# PinWheelV2.net
KiCad netlist of a schematic drawn in Altium Designer
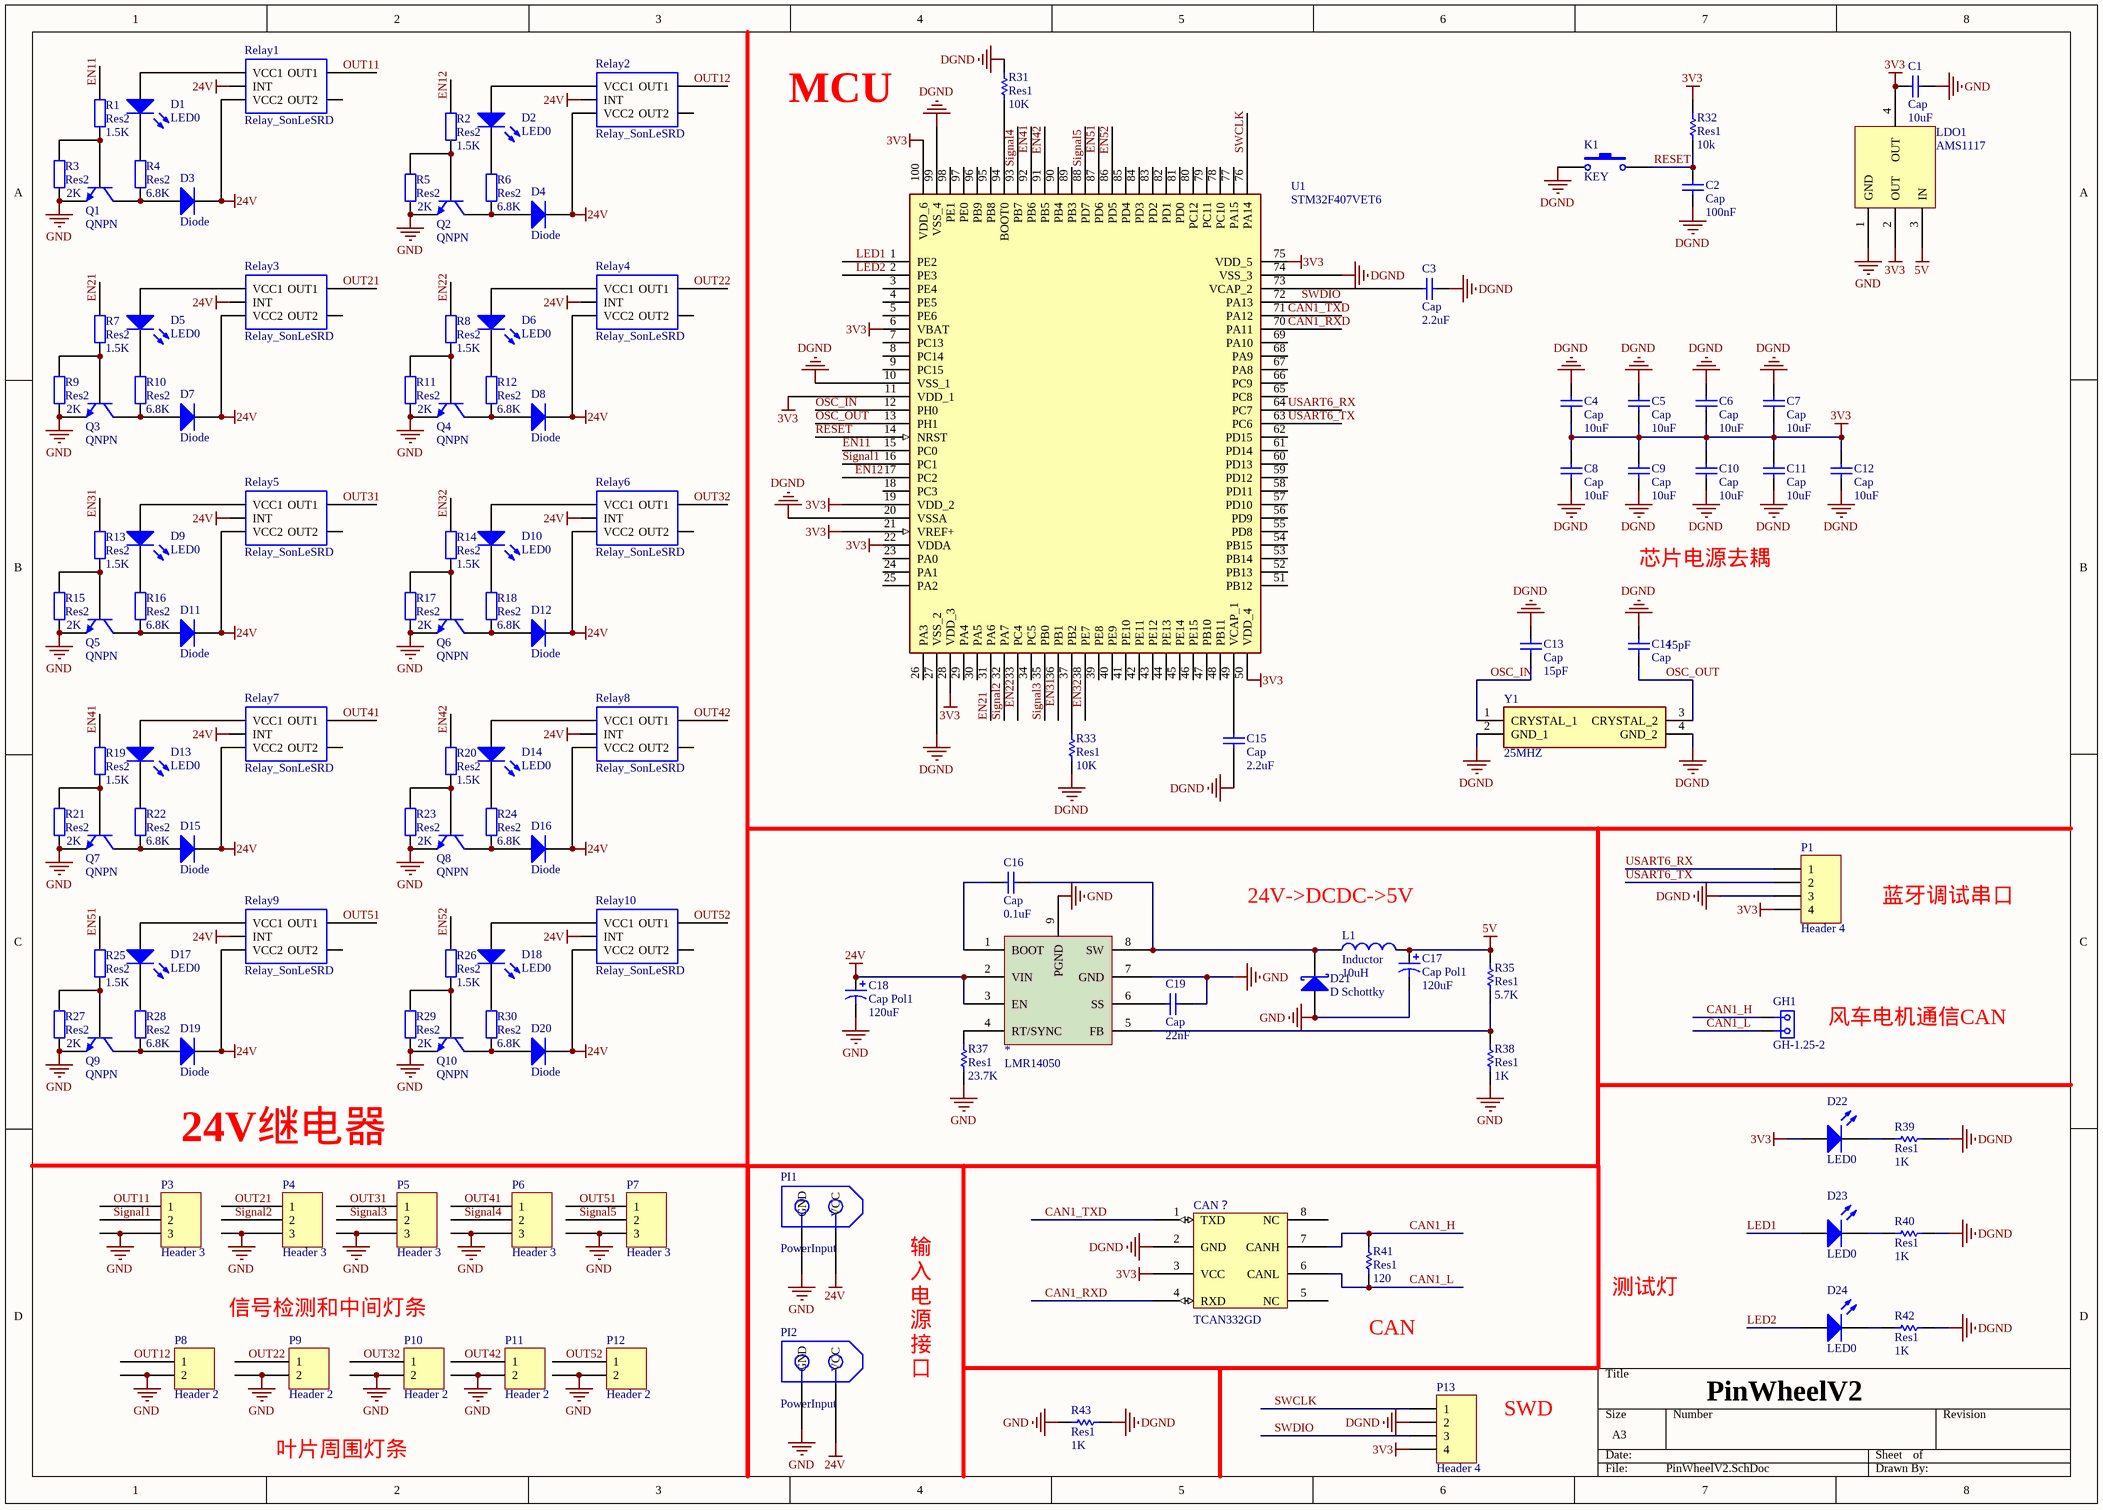
[diagram p0: PinWheelV2.SchDoc]

(export (version "E")
  (design (tool "Eeschema 10.0.6"))
  (components
    (comp (ref "*") (value "LMR14050") (footprint "LMR14050") (libsource (lib "PinWheel") (part "LMR14050")))
    (comp (ref "C1")
      (value "Cap")
      (footprint "R 0603")
      (description "Capacitor")
      (fields (field (name "ALTIUM_VALUE") "10uF") (field (name "PUBLISHER") "Altium Limited"))
      (libsource (lib "Miscellaneous Devices") (part "Cap"))
    )
    (comp (ref "C2")
      (value "Cap")
      (footprint "R 0603")
      (description "Capacitor")
      (fields (field (name "ALTIUM_VALUE") "100nF") (field (name "PUBLISHER") "Altium Limited"))
      (libsource (lib "Miscellaneous Devices") (part "Cap"))
    )
    (comp (ref "C3")
      (value "Cap")
      (footprint "R 0603")
      (description "Capacitor")
      (fields (field (name "ALTIUM_VALUE") "2.2uF") (field (name "PUBLISHER") "Altium Limited"))
      (libsource (lib "Miscellaneous Devices") (part "Cap"))
    )
    (comp (ref "C4")
      (value "Cap")
      (footprint "R 0603")
      (description "Capacitor")
      (fields (field (name "ALTIUM_VALUE") "10uF") (field (name "PUBLISHER") "Altium Limited"))
      (libsource (lib "Miscellaneous Devices") (part "Cap"))
    )
    (comp (ref "C5")
      (value "Cap")
      (footprint "R 0603")
      (description "Capacitor")
      (fields (field (name "ALTIUM_VALUE") "10uF") (field (name "PUBLISHER") "Altium Limited"))
      (libsource (lib "Miscellaneous Devices") (part "Cap"))
    )
    (comp (ref "C6")
      (value "Cap")
      (footprint "R 0603")
      (description "Capacitor")
      (fields (field (name "ALTIUM_VALUE") "10uF") (field (name "PUBLISHER") "Altium Limited"))
      (libsource (lib "Miscellaneous Devices") (part "Cap"))
    )
    (comp (ref "C7")
      (value "Cap")
      (footprint "R 0603")
      (description "Capacitor")
      (fields (field (name "ALTIUM_VALUE") "10uF") (field (name "PUBLISHER") "Altium Limited"))
      (libsource (lib "Miscellaneous Devices") (part "Cap"))
    )
    (comp (ref "C8")
      (value "Cap")
      (footprint "R 0603")
      (description "Capacitor")
      (fields (field (name "ALTIUM_VALUE") "10uF") (field (name "PUBLISHER") "Altium Limited"))
      (libsource (lib "Miscellaneous Devices") (part "Cap"))
    )
    (comp (ref "C9")
      (value "Cap")
      (footprint "R 0603")
      (description "Capacitor")
      (fields (field (name "ALTIUM_VALUE") "10uF") (field (name "PUBLISHER") "Altium Limited"))
      (libsource (lib "Miscellaneous Devices") (part "Cap"))
    )
    (comp (ref "C10")
      (value "Cap")
      (footprint "R 0603")
      (description "Capacitor")
      (fields (field (name "ALTIUM_VALUE") "10uF") (field (name "PUBLISHER") "Altium Limited"))
      (libsource (lib "Miscellaneous Devices") (part "Cap"))
    )
    (comp (ref "C11")
      (value "Cap")
      (footprint "R 0603")
      (description "Capacitor")
      (fields (field (name "ALTIUM_VALUE") "10uF") (field (name "PUBLISHER") "Altium Limited"))
      (libsource (lib "Miscellaneous Devices") (part "Cap"))
    )
    (comp (ref "C12")
      (value "Cap")
      (footprint "R 0603")
      (description "Capacitor")
      (fields (field (name "ALTIUM_VALUE") "10uF") (field (name "PUBLISHER") "Altium Limited"))
      (libsource (lib "Miscellaneous Devices") (part "Cap"))
    )
    (comp (ref "C13")
      (value "Cap")
      (footprint "R 0603")
      (description "Capacitor")
      (fields (field (name "ALTIUM_VALUE") "15pF") (field (name "PUBLISHER") "Altium Limited"))
      (libsource (lib "Miscellaneous Devices") (part "Cap"))
    )
    (comp (ref "C14")
      (value "Cap")
      (footprint "R 0603")
      (description "Capacitor")
      (fields (field (name "ALTIUM_VALUE") "15pF") (field (name "PUBLISHER") "Altium Limited"))
      (libsource (lib "Miscellaneous Devices") (part "Cap"))
    )
    (comp (ref "C15")
      (value "Cap")
      (footprint "R 0603")
      (description "Capacitor")
      (fields (field (name "ALTIUM_VALUE") "2.2uF") (field (name "PUBLISHER") "Altium Limited"))
      (libsource (lib "Miscellaneous Devices") (part "Cap"))
    )
    (comp (ref "C16")
      (value "Cap")
      (footprint "R 0603")
      (description "Capacitor")
      (fields (field (name "ALTIUM_VALUE") "0.1uF") (field (name "PUBLISHER") "Altium Limited"))
      (libsource (lib "Miscellaneous Devices") (part "Cap"))
    )
    (comp (ref "C17")
      (value "Cap Pol1")
      (footprint "Cap+8*11")
      (description "Polarized Capacitor (Radial)")
      (fields (field (name "ALTIUM_VALUE") "120uF") (field (name "PUBLISHER") "Altium Limited"))
      (libsource (lib "Miscellaneous Devices") (part "Cap Pol1"))
    )
    (comp (ref "C18")
      (value "Cap Pol1")
      (footprint "Cap+8*11")
      (description "Polarized Capacitor (Radial)")
      (fields (field (name "ALTIUM_VALUE") "120uF") (field (name "PUBLISHER") "Altium Limited"))
      (libsource (lib "Miscellaneous Devices") (part "Cap Pol1"))
    )
    (comp (ref "C19")
      (value "Cap")
      (footprint "R 0603")
      (description "Capacitor")
      (fields (field (name "ALTIUM_VALUE") "22nF") (field (name "PUBLISHER") "Altium Limited"))
      (libsource (lib "Miscellaneous Devices") (part "Cap"))
    )
    (comp (ref "CAN？")
      (value "TCAN332GD")
      (footprint "LMR14050")
      (libsource (lib "PinWheel") (part "TCAN332GD"))
    )
    (comp (ref "D1")
      (value "LED0")
      (footprint "LED 0603")
      (description "Typical INFRARED GaAs LED")
      (fields (field (name "PUBLISHER") "Altium Limited"))
      (libsource (lib "Miscellaneous Devices") (part "LED0"))
    )
    (comp (ref "D2")
      (value "LED0")
      (footprint "LED 0603")
      (description "Typical INFRARED GaAs LED")
      (fields (field (name "PUBLISHER") "Altium Limited"))
      (libsource (lib "Miscellaneous Devices") (part "LED0"))
    )
    (comp (ref "D3")
      (value "Diode")
      (footprint "1N4007 D")
      (description "Default Diode")
      (fields (field (name "PUBLISHER") "Altium Limited"))
      (libsource (lib "Miscellaneous Devices") (part "Diode"))
    )
    (comp (ref "D4")
      (value "Diode")
      (footprint "1N4007 D")
      (description "Default Diode")
      (fields (field (name "PUBLISHER") "Altium Limited"))
      (libsource (lib "Miscellaneous Devices") (part "Diode"))
    )
    (comp (ref "D5")
      (value "LED0")
      (footprint "LED 0603")
      (description "Typical INFRARED GaAs LED")
      (fields (field (name "PUBLISHER") "Altium Limited"))
      (libsource (lib "Miscellaneous Devices") (part "LED0"))
    )
    (comp (ref "D6")
      (value "LED0")
      (footprint "LED 0603")
      (description "Typical INFRARED GaAs LED")
      (fields (field (name "PUBLISHER") "Altium Limited"))
      (libsource (lib "Miscellaneous Devices") (part "LED0"))
    )
    (comp (ref "D7")
      (value "Diode")
      (footprint "1N4007 D")
      (description "Default Diode")
      (fields (field (name "PUBLISHER") "Altium Limited"))
      (libsource (lib "Miscellaneous Devices") (part "Diode"))
    )
    (comp (ref "D8")
      (value "Diode")
      (footprint "1N4007 D")
      (description "Default Diode")
      (fields (field (name "PUBLISHER") "Altium Limited"))
      (libsource (lib "Miscellaneous Devices") (part "Diode"))
    )
    (comp (ref "D9")
      (value "LED0")
      (footprint "LED 0603")
      (description "Typical INFRARED GaAs LED")
      (fields (field (name "PUBLISHER") "Altium Limited"))
      (libsource (lib "Miscellaneous Devices") (part "LED0"))
    )
    (comp (ref "D10")
      (value "LED0")
      (footprint "LED 0603")
      (description "Typical INFRARED GaAs LED")
      (fields (field (name "PUBLISHER") "Altium Limited"))
      (libsource (lib "Miscellaneous Devices") (part "LED0"))
    )
    (comp (ref "D11")
      (value "Diode")
      (footprint "1N4007 D")
      (description "Default Diode")
      (fields (field (name "PUBLISHER") "Altium Limited"))
      (libsource (lib "Miscellaneous Devices") (part "Diode"))
    )
    (comp (ref "D12")
      (value "Diode")
      (footprint "1N4007 D")
      (description "Default Diode")
      (fields (field (name "PUBLISHER") "Altium Limited"))
      (libsource (lib "Miscellaneous Devices") (part "Diode"))
    )
    (comp (ref "D13")
      (value "LED0")
      (footprint "LED 0603")
      (description "Typical INFRARED GaAs LED")
      (fields (field (name "PUBLISHER") "Altium Limited"))
      (libsource (lib "Miscellaneous Devices") (part "LED0"))
    )
    (comp (ref "D14")
      (value "LED0")
      (footprint "LED 0603")
      (description "Typical INFRARED GaAs LED")
      (fields (field (name "PUBLISHER") "Altium Limited"))
      (libsource (lib "Miscellaneous Devices") (part "LED0"))
    )
    (comp (ref "D15")
      (value "Diode")
      (footprint "1N4007 D")
      (description "Default Diode")
      (fields (field (name "PUBLISHER") "Altium Limited"))
      (libsource (lib "Miscellaneous Devices") (part "Diode"))
    )
    (comp (ref "D16")
      (value "Diode")
      (footprint "1N4007 D")
      (description "Default Diode")
      (fields (field (name "PUBLISHER") "Altium Limited"))
      (libsource (lib "Miscellaneous Devices") (part "Diode"))
    )
    (comp (ref "D17")
      (value "LED0")
      (footprint "LED 0603")
      (description "Typical INFRARED GaAs LED")
      (fields (field (name "PUBLISHER") "Altium Limited"))
      (libsource (lib "Miscellaneous Devices") (part "LED0"))
    )
    (comp (ref "D18")
      (value "LED0")
      (footprint "LED 0603")
      (description "Typical INFRARED GaAs LED")
      (fields (field (name "PUBLISHER") "Altium Limited"))
      (libsource (lib "Miscellaneous Devices") (part "LED0"))
    )
    (comp (ref "D19")
      (value "Diode")
      (footprint "1N4007 D")
      (description "Default Diode")
      (fields (field (name "PUBLISHER") "Altium Limited"))
      (libsource (lib "Miscellaneous Devices") (part "Diode"))
    )
    (comp (ref "D20")
      (value "Diode")
      (footprint "1N4007 D")
      (description "Default Diode")
      (fields (field (name "PUBLISHER") "Altium Limited"))
      (libsource (lib "Miscellaneous Devices") (part "Diode"))
    )
    (comp (ref "D21")
      (value "D Schottky")
      (footprint "SMB")
      (description "Schottky Diode")
      (fields (field (name "PUBLISHER") "Altium Limited"))
      (libsource (lib "Miscellaneous Devices") (part "D Schottky"))
    )
    (comp (ref "D22")
      (value "LED0")
      (footprint "LED 0603")
      (description "Typical INFRARED GaAs LED")
      (fields (field (name "PUBLISHER") "Altium Limited"))
      (libsource (lib "Miscellaneous Devices") (part "LED0"))
    )
    (comp (ref "D23")
      (value "LED0")
      (footprint "LED 0603")
      (description "Typical INFRARED GaAs LED")
      (fields (field (name "PUBLISHER") "Altium Limited"))
      (libsource (lib "Miscellaneous Devices") (part "LED0"))
    )
    (comp (ref "D24")
      (value "LED0")
      (footprint "LED 0603")
      (description "Typical INFRARED GaAs LED")
      (fields (field (name "PUBLISHER") "Altium Limited"))
      (libsource (lib "Miscellaneous Devices") (part "LED0"))
    )
    (comp (ref "GH1")
      (value "GH-1.25-2")
      (footprint "GH1.25_2P")
      (libsource (lib "Personal_Integrated_Library") (part "GH-1.25-2"))
    )
    (comp (ref "K1") (value "KEY") (footprint "keySMD3.5*6") (libsource (lib "PinWheel") (part "KEY")))
    (comp (ref "L1")
      (value "Inductor")
      (footprint "L 3.5*3*2.1")
      (fields (field (name "ALTIUM_VALUE") "10uH") (field (name "PUBLISHER") "Altium Limited"))
      (libsource (lib "Miscellaneous Devices") (part "Inductor"))
    )
    (comp (ref "LDO1")
      (value "AMS1117")
      (footprint "AMS1117 3V3")
      (libsource (lib "Personal_Integrated_Library") (part "AMS1117"))
    )
    (comp (ref "P1")
      (value "Header 4")
      (footprint "HDR1X4")
      (description "Header, 4-Pin")
      (fields (field (name "PUBLISHER") "Altium Limited"))
      (libsource (lib "Miscellaneous Connectors") (part "Header 4"))
    )
    (comp (ref "P3")
      (value "Header 3")
      (footprint "螺旋端子 3P3.81")
      (description "Header, 3-Pin")
      (fields (field (name "PUBLISHER") "Altium Limited"))
      (libsource (lib "Miscellaneous Connectors") (part "Header 3"))
    )
    (comp (ref "P4")
      (value "Header 3")
      (footprint "螺旋端子 3P3.81")
      (description "Header, 3-Pin")
      (fields (field (name "PUBLISHER") "Altium Limited"))
      (libsource (lib "Miscellaneous Connectors") (part "Header 3"))
    )
    (comp (ref "P5")
      (value "Header 3")
      (footprint "螺旋端子 3P3.81")
      (description "Header, 3-Pin")
      (fields (field (name "PUBLISHER") "Altium Limited"))
      (libsource (lib "Miscellaneous Connectors") (part "Header 3"))
    )
    (comp (ref "P6")
      (value "Header 3")
      (footprint "螺旋端子 3P3.81")
      (description "Header, 3-Pin")
      (fields (field (name "PUBLISHER") "Altium Limited"))
      (libsource (lib "Miscellaneous Connectors") (part "Header 3"))
    )
    (comp (ref "P7")
      (value "Header 3")
      (footprint "螺旋端子 3P3.81")
      (description "Header, 3-Pin")
      (fields (field (name "PUBLISHER") "Altium Limited"))
      (libsource (lib "Miscellaneous Connectors") (part "Header 3"))
    )
    (comp (ref "P8")
      (value "Header 2")
      (footprint "螺旋端子 2P3.81")
      (description "Header, 2-Pin")
      (fields (field (name "PUBLISHER") "Altium Limited"))
      (libsource (lib "Miscellaneous Connectors") (part "Header 2"))
    )
    (comp (ref "P9")
      (value "Header 2")
      (footprint "螺旋端子 2P3.81")
      (description "Header, 2-Pin")
      (fields (field (name "PUBLISHER") "Altium Limited"))
      (libsource (lib "Miscellaneous Connectors") (part "Header 2"))
    )
    (comp (ref "P10")
      (value "Header 2")
      (footprint "螺旋端子 2P3.81")
      (description "Header, 2-Pin")
      (fields (field (name "PUBLISHER") "Altium Limited"))
      (libsource (lib "Miscellaneous Connectors") (part "Header 2"))
    )
    (comp (ref "P11")
      (value "Header 2")
      (footprint "螺旋端子 2P3.81")
      (description "Header, 2-Pin")
      (fields (field (name "PUBLISHER") "Altium Limited"))
      (libsource (lib "Miscellaneous Connectors") (part "Header 2"))
    )
    (comp (ref "P12")
      (value "Header 2")
      (footprint "螺旋端子 2P3.81")
      (description "Header, 2-Pin")
      (fields (field (name "PUBLISHER") "Altium Limited"))
      (libsource (lib "Miscellaneous Connectors") (part "Header 2"))
    )
    (comp (ref "P13")
      (value "Header 4")
      (footprint "HDR1X4")
      (description "Header, 4-Pin")
      (fields (field (name "PUBLISHER") "Altium Limited"))
      (libsource (lib "Miscellaneous Connectors") (part "Header 4"))
    )
    (comp (ref "PI1") (value "PowerInput") (footprint "XT30") (libsource (lib "Schlib1") (part "PowerInput")))
    (comp (ref "PI2") (value "PowerInput") (footprint "XT30") (libsource (lib "Schlib1") (part "PowerInput")))
    (comp (ref "Q1")
      (value "QNPN")
      (footprint "MMBT2222A")
      (description "NPN Bipolar Transistor")
      (fields (field (name "PUBLISHER") "Altium Limited"))
      (libsource (lib "Miscellaneous Devices") (part "QNPN"))
    )
    (comp (ref "Q2")
      (value "QNPN")
      (footprint "MMBT2222A")
      (description "NPN Bipolar Transistor")
      (fields (field (name "PUBLISHER") "Altium Limited"))
      (libsource (lib "Miscellaneous Devices") (part "QNPN"))
    )
    (comp (ref "Q3")
      (value "QNPN")
      (footprint "MMBT2222A")
      (description "NPN Bipolar Transistor")
      (fields (field (name "PUBLISHER") "Altium Limited"))
      (libsource (lib "Miscellaneous Devices") (part "QNPN"))
    )
    (comp (ref "Q4")
      (value "QNPN")
      (footprint "MMBT2222A")
      (description "NPN Bipolar Transistor")
      (fields (field (name "PUBLISHER") "Altium Limited"))
      (libsource (lib "Miscellaneous Devices") (part "QNPN"))
    )
    (comp (ref "Q5")
      (value "QNPN")
      (footprint "MMBT2222A")
      (description "NPN Bipolar Transistor")
      (fields (field (name "PUBLISHER") "Altium Limited"))
      (libsource (lib "Miscellaneous Devices") (part "QNPN"))
    )
    (comp (ref "Q6")
      (value "QNPN")
      (footprint "MMBT2222A")
      (description "NPN Bipolar Transistor")
      (fields (field (name "PUBLISHER") "Altium Limited"))
      (libsource (lib "Miscellaneous Devices") (part "QNPN"))
    )
    (comp (ref "Q7")
      (value "QNPN")
      (footprint "MMBT2222A")
      (description "NPN Bipolar Transistor")
      (fields (field (name "PUBLISHER") "Altium Limited"))
      (libsource (lib "Miscellaneous Devices") (part "QNPN"))
    )
    (comp (ref "Q8")
      (value "QNPN")
      (footprint "MMBT2222A")
      (description "NPN Bipolar Transistor")
      (fields (field (name "PUBLISHER") "Altium Limited"))
      (libsource (lib "Miscellaneous Devices") (part "QNPN"))
    )
    (comp (ref "Q9")
      (value "QNPN")
      (footprint "MMBT2222A")
      (description "NPN Bipolar Transistor")
      (fields (field (name "PUBLISHER") "Altium Limited"))
      (libsource (lib "Miscellaneous Devices") (part "QNPN"))
    )
    (comp (ref "Q10")
      (value "QNPN")
      (footprint "MMBT2222A")
      (description "NPN Bipolar Transistor")
      (fields (field (name "PUBLISHER") "Altium Limited"))
      (libsource (lib "Miscellaneous Devices") (part "QNPN"))
    )
    (comp (ref "R1")
      (value "Res2")
      (footprint "R 0603")
      (description "Resistor")
      (fields (field (name "ALTIUM_VALUE") "1.5K") (field (name "PUBLISHER") "Altium Limited"))
      (libsource (lib "Miscellaneous Devices") (part "Res2"))
    )
    (comp (ref "R2")
      (value "Res2")
      (footprint "R 0603")
      (description "Resistor")
      (fields (field (name "ALTIUM_VALUE") "1.5K") (field (name "PUBLISHER") "Altium Limited"))
      (libsource (lib "Miscellaneous Devices") (part "Res2"))
    )
    (comp (ref "R3")
      (value "Res2")
      (footprint "R 0603")
      (description "Resistor")
      (fields (field (name "ALTIUM_VALUE") "2K") (field (name "PUBLISHER") "Altium Limited"))
      (libsource (lib "Miscellaneous Devices") (part "Res2"))
    )
    (comp (ref "R4")
      (value "Res2")
      (footprint "R 0603")
      (description "Resistor")
      (fields (field (name "ALTIUM_VALUE") "6.8K") (field (name "PUBLISHER") "Altium Limited"))
      (libsource (lib "Miscellaneous Devices") (part "Res2"))
    )
    (comp (ref "R5")
      (value "Res2")
      (footprint "R 0603")
      (description "Resistor")
      (fields (field (name "ALTIUM_VALUE") "2K") (field (name "PUBLISHER") "Altium Limited"))
      (libsource (lib "Miscellaneous Devices") (part "Res2"))
    )
    (comp (ref "R6")
      (value "Res2")
      (footprint "R 0603")
      (description "Resistor")
      (fields (field (name "ALTIUM_VALUE") "6.8K") (field (name "PUBLISHER") "Altium Limited"))
      (libsource (lib "Miscellaneous Devices") (part "Res2"))
    )
    (comp (ref "R7")
      (value "Res2")
      (footprint "R 0603")
      (description "Resistor")
      (fields (field (name "ALTIUM_VALUE") "1.5K") (field (name "PUBLISHER") "Altium Limited"))
      (libsource (lib "Miscellaneous Devices") (part "Res2"))
    )
    (comp (ref "R8")
      (value "Res2")
      (footprint "R 0603")
      (description "Resistor")
      (fields (field (name "ALTIUM_VALUE") "1.5K") (field (name "PUBLISHER") "Altium Limited"))
      (libsource (lib "Miscellaneous Devices") (part "Res2"))
    )
    (comp (ref "R9")
      (value "Res2")
      (footprint "R 0603")
      (description "Resistor")
      (fields (field (name "ALTIUM_VALUE") "2K") (field (name "PUBLISHER") "Altium Limited"))
      (libsource (lib "Miscellaneous Devices") (part "Res2"))
    )
    (comp (ref "R10")
      (value "Res2")
      (footprint "R 0603")
      (description "Resistor")
      (fields (field (name "ALTIUM_VALUE") "6.8K") (field (name "PUBLISHER") "Altium Limited"))
      (libsource (lib "Miscellaneous Devices") (part "Res2"))
    )
    (comp (ref "R11")
      (value "Res2")
      (footprint "R 0603")
      (description "Resistor")
      (fields (field (name "ALTIUM_VALUE") "2K") (field (name "PUBLISHER") "Altium Limited"))
      (libsource (lib "Miscellaneous Devices") (part "Res2"))
    )
    (comp (ref "R12")
      (value "Res2")
      (footprint "R 0603")
      (description "Resistor")
      (fields (field (name "ALTIUM_VALUE") "6.8K") (field (name "PUBLISHER") "Altium Limited"))
      (libsource (lib "Miscellaneous Devices") (part "Res2"))
    )
    (comp (ref "R13")
      (value "Res2")
      (footprint "R 0603")
      (description "Resistor")
      (fields (field (name "ALTIUM_VALUE") "1.5K") (field (name "PUBLISHER") "Altium Limited"))
      (libsource (lib "Miscellaneous Devices") (part "Res2"))
    )
    (comp (ref "R14")
      (value "Res2")
      (footprint "R 0603")
      (description "Resistor")
      (fields (field (name "ALTIUM_VALUE") "1.5K") (field (name "PUBLISHER") "Altium Limited"))
      (libsource (lib "Miscellaneous Devices") (part "Res2"))
    )
    (comp (ref "R15")
      (value "Res2")
      (footprint "R 0603")
      (description "Resistor")
      (fields (field (name "ALTIUM_VALUE") "2K") (field (name "PUBLISHER") "Altium Limited"))
      (libsource (lib "Miscellaneous Devices") (part "Res2"))
    )
    (comp (ref "R16")
      (value "Res2")
      (footprint "R 0603")
      (description "Resistor")
      (fields (field (name "ALTIUM_VALUE") "6.8K") (field (name "PUBLISHER") "Altium Limited"))
      (libsource (lib "Miscellaneous Devices") (part "Res2"))
    )
    (comp (ref "R17")
      (value "Res2")
      (footprint "R 0603")
      (description "Resistor")
      (fields (field (name "ALTIUM_VALUE") "2K") (field (name "PUBLISHER") "Altium Limited"))
      (libsource (lib "Miscellaneous Devices") (part "Res2"))
    )
    (comp (ref "R18")
      (value "Res2")
      (footprint "R 0603")
      (description "Resistor")
      (fields (field (name "ALTIUM_VALUE") "6.8K") (field (name "PUBLISHER") "Altium Limited"))
      (libsource (lib "Miscellaneous Devices") (part "Res2"))
    )
    (comp (ref "R19")
      (value "Res2")
      (footprint "R 0603")
      (description "Resistor")
      (fields (field (name "ALTIUM_VALUE") "1.5K") (field (name "PUBLISHER") "Altium Limited"))
      (libsource (lib "Miscellaneous Devices") (part "Res2"))
    )
    (comp (ref "R20")
      (value "Res2")
      (footprint "R 0603")
      (description "Resistor")
      (fields (field (name "ALTIUM_VALUE") "1.5K") (field (name "PUBLISHER") "Altium Limited"))
      (libsource (lib "Miscellaneous Devices") (part "Res2"))
    )
    (comp (ref "R21")
      (value "Res2")
      (footprint "R 0603")
      (description "Resistor")
      (fields (field (name "ALTIUM_VALUE") "2K") (field (name "PUBLISHER") "Altium Limited"))
      (libsource (lib "Miscellaneous Devices") (part "Res2"))
    )
    (comp (ref "R22")
      (value "Res2")
      (footprint "R 0603")
      (description "Resistor")
      (fields (field (name "ALTIUM_VALUE") "6.8K") (field (name "PUBLISHER") "Altium Limited"))
      (libsource (lib "Miscellaneous Devices") (part "Res2"))
    )
    (comp (ref "R23")
      (value "Res2")
      (footprint "R 0603")
      (description "Resistor")
      (fields (field (name "ALTIUM_VALUE") "2K") (field (name "PUBLISHER") "Altium Limited"))
      (libsource (lib "Miscellaneous Devices") (part "Res2"))
    )
    (comp (ref "R24")
      (value "Res2")
      (footprint "R 0603")
      (description "Resistor")
      (fields (field (name "ALTIUM_VALUE") "6.8K") (field (name "PUBLISHER") "Altium Limited"))
      (libsource (lib "Miscellaneous Devices") (part "Res2"))
    )
    (comp (ref "R25")
      (value "Res2")
      (footprint "R 0603")
      (description "Resistor")
      (fields (field (name "ALTIUM_VALUE") "1.5K") (field (name "PUBLISHER") "Altium Limited"))
      (libsource (lib "Miscellaneous Devices") (part "Res2"))
    )
    (comp (ref "R26")
      (value "Res2")
      (footprint "R 0603")
      (description "Resistor")
      (fields (field (name "ALTIUM_VALUE") "1.5K") (field (name "PUBLISHER") "Altium Limited"))
      (libsource (lib "Miscellaneous Devices") (part "Res2"))
    )
    (comp (ref "R27")
      (value "Res2")
      (footprint "R 0603")
      (description "Resistor")
      (fields (field (name "ALTIUM_VALUE") "2K") (field (name "PUBLISHER") "Altium Limited"))
      (libsource (lib "Miscellaneous Devices") (part "Res2"))
    )
    (comp (ref "R28")
      (value "Res2")
      (footprint "R 0603")
      (description "Resistor")
      (fields (field (name "ALTIUM_VALUE") "6.8K") (field (name "PUBLISHER") "Altium Limited"))
      (libsource (lib "Miscellaneous Devices") (part "Res2"))
    )
    (comp (ref "R29")
      (value "Res2")
      (footprint "R 0603")
      (description "Resistor")
      (fields (field (name "ALTIUM_VALUE") "2K") (field (name "PUBLISHER") "Altium Limited"))
      (libsource (lib "Miscellaneous Devices") (part "Res2"))
    )
    (comp (ref "R30")
      (value "Res2")
      (footprint "R 0603")
      (description "Resistor")
      (fields (field (name "ALTIUM_VALUE") "6.8K") (field (name "PUBLISHER") "Altium Limited"))
      (libsource (lib "Miscellaneous Devices") (part "Res2"))
    )
    (comp (ref "R31")
      (value "Res1")
      (footprint "R 0603")
      (description "Resistor")
      (fields (field (name "ALTIUM_VALUE") "10K") (field (name "PUBLISHER") "Altium Limited"))
      (libsource (lib "Miscellaneous Devices") (part "Res1"))
    )
    (comp (ref "R32")
      (value "Res1")
      (footprint "R 0603")
      (description "Resistor")
      (fields (field (name "ALTIUM_VALUE") "10k") (field (name "PUBLISHER") "Altium Limited"))
      (libsource (lib "Miscellaneous Devices") (part "Res1"))
    )
    (comp (ref "R33")
      (value "Res1")
      (footprint "R 0603")
      (description "Resistor")
      (fields (field (name "ALTIUM_VALUE") "10K") (field (name "PUBLISHER") "Altium Limited"))
      (libsource (lib "Miscellaneous Devices") (part "Res1"))
    )
    (comp (ref "R35")
      (value "Res1")
      (footprint "R 0603")
      (description "Resistor")
      (fields (field (name "ALTIUM_VALUE") "5.7K") (field (name "PUBLISHER") "Altium Limited"))
      (libsource (lib "Miscellaneous Devices") (part "Res1"))
    )
    (comp (ref "R37")
      (value "Res1")
      (footprint "R 0603")
      (description "Resistor")
      (fields (field (name "ALTIUM_VALUE") "23.7K") (field (name "PUBLISHER") "Altium Limited"))
      (libsource (lib "Miscellaneous Devices") (part "Res1"))
    )
    (comp (ref "R38")
      (value "Res1")
      (footprint "R 0603")
      (description "Resistor")
      (fields (field (name "ALTIUM_VALUE") "1K") (field (name "PUBLISHER") "Altium Limited"))
      (libsource (lib "Miscellaneous Devices") (part "Res1"))
    )
    (comp (ref "R39")
      (value "Res1")
      (footprint "R 0603")
      (description "Resistor")
      (fields (field (name "ALTIUM_VALUE") "1K") (field (name "PUBLISHER") "Altium Limited"))
      (libsource (lib "Miscellaneous Devices") (part "Res1"))
    )
    (comp (ref "R40")
      (value "Res1")
      (footprint "R 0603")
      (description "Resistor")
      (fields (field (name "ALTIUM_VALUE") "1K") (field (name "PUBLISHER") "Altium Limited"))
      (libsource (lib "Miscellaneous Devices") (part "Res1"))
    )
    (comp (ref "R41")
      (value "Res1")
      (footprint "R 0603")
      (description "Resistor")
      (fields (field (name "ALTIUM_VALUE") "120") (field (name "PUBLISHER") "Altium Limited"))
      (libsource (lib "Miscellaneous Devices") (part "Res1"))
    )
    (comp (ref "R42")
      (value "Res1")
      (footprint "R 0603")
      (description "Resistor")
      (fields (field (name "ALTIUM_VALUE") "1K") (field (name "PUBLISHER") "Altium Limited"))
      (libsource (lib "Miscellaneous Devices") (part "Res1"))
    )
    (comp (ref "R43")
      (value "Res1")
      (footprint "R 0603")
      (description "Resistor")
      (fields (field (name "ALTIUM_VALUE") "1K") (field (name "PUBLISHER") "Altium Limited"))
      (libsource (lib "Miscellaneous Devices") (part "Res1"))
    )
    (comp (ref "Relay1")
      (value "Relay_SonLeSRD")
      (footprint "RePlay_SonLe")
      (libsource (lib "Schlib1") (part "Relay_SonLeSRD"))
    )
    (comp (ref "Relay2")
      (value "Relay_SonLeSRD")
      (footprint "RePlay_SonLe")
      (libsource (lib "Schlib1") (part "Relay_SonLeSRD"))
    )
    (comp (ref "Relay3")
      (value "Relay_SonLeSRD")
      (footprint "RePlay_SonLe")
      (libsource (lib "Schlib1") (part "Relay_SonLeSRD"))
    )
    (comp (ref "Relay4")
      (value "Relay_SonLeSRD")
      (footprint "RePlay_SonLe")
      (libsource (lib "Schlib1") (part "Relay_SonLeSRD"))
    )
    (comp (ref "Relay5")
      (value "Relay_SonLeSRD")
      (footprint "RePlay_SonLe")
      (libsource (lib "Schlib1") (part "Relay_SonLeSRD"))
    )
    (comp (ref "Relay6")
      (value "Relay_SonLeSRD")
      (footprint "RePlay_SonLe")
      (libsource (lib "Schlib1") (part "Relay_SonLeSRD"))
    )
    (comp (ref "Relay7")
      (value "Relay_SonLeSRD")
      (footprint "RePlay_SonLe")
      (libsource (lib "Schlib1") (part "Relay_SonLeSRD"))
    )
    (comp (ref "Relay8")
      (value "Relay_SonLeSRD")
      (footprint "RePlay_SonLe")
      (libsource (lib "Schlib1") (part "Relay_SonLeSRD"))
    )
    (comp (ref "Relay9")
      (value "Relay_SonLeSRD")
      (footprint "RePlay_SonLe")
      (libsource (lib "Schlib1") (part "Relay_SonLeSRD"))
    )
    (comp (ref "Relay10")
      (value "Relay_SonLeSRD")
      (footprint "RePlay_SonLe")
      (libsource (lib "Schlib1") (part "Relay_SonLeSRD"))
    )
    (comp (ref "U1")
      (value "STM32F407VET6")
      (footprint "STM32F407VET6")
      (libsource (lib "PinWheel") (part "STM32F407VET6"))
    )
    (comp (ref "Y1")
      (value "25MHZ")
      (footprint "晶振 3.2*2.5")
      (description "Crystal or Oscillator")
      (fields
        (field (name "MOUSER PART NUMBER") "815-M11AIG-25-4ZT3")
        (field (name "MANUFACTURER_PART_NUMBER") "ABM11AIG-25.000MHZ-4Z-T3")
      )
      (libsource (lib "SamacSys") (part "ABM11AIG-25.000MHZ-4Z-T3"))
    )
  )
  (nets
    (net (code "1") (name "/CAN1_H") (class "Default")
      (node (ref "CAN？") (pin "7") (pinfunction "CANH_7") (pintype "power_in"))
      (node (ref "GH1") (pin "1") (pinfunction "1_1") (pintype "power_in"))
      (node (ref "R41") (pin "2") (pinfunction "2_2") (pintype "passive"))
    )
    (net (code "2") (name "/CAN1_L") (class "Default")
      (node (ref "CAN？") (pin "6") (pinfunction "CANL_6") (pintype "power_in"))
      (node (ref "GH1") (pin "2") (pinfunction "2_2") (pintype "power_in"))
      (node (ref "R41") (pin "1") (pinfunction "1_1") (pintype "passive"))
    )
    (net (code "3") (name "/CAN1_RXD") (class "Default")
      (node (ref "CAN？") (pin "4") (pinfunction "RXD_4") (pintype "bidirectional"))
      (node (ref "U1") (pin "70") (pinfunction "PA11_70") (pintype "passive"))
    )
    (net (code "4") (name "/CAN1_TXD") (class "Default")
      (node (ref "CAN？") (pin "1") (pinfunction "TXD_1") (pintype "bidirectional"))
      (node (ref "U1") (pin "71") (pinfunction "PA12_71") (pintype "passive"))
    )
    (net (code "5") (name "/EN11") (class "Default")
      (node (ref "R1") (pin "2") (pinfunction "2_2") (pintype "passive"))
      (node (ref "U1") (pin "15") (pinfunction "PC0_15") (pintype "passive"))
    )
    (net (code "6") (name "/EN12") (class "Default")
      (node (ref "R2") (pin "2") (pinfunction "2_2") (pintype "passive"))
      (node (ref "U1") (pin "17") (pinfunction "PC2_17") (pintype "passive"))
    )
    (net (code "7") (name "/EN21") (class "Default")
      (node (ref "R7") (pin "2") (pinfunction "2_2") (pintype "passive"))
      (node (ref "U1") (pin "31") (pinfunction "PA6_31") (pintype "passive"))
    )
    (net (code "8") (name "/EN22") (class "Default")
      (node (ref "R8") (pin "2") (pinfunction "2_2") (pintype "passive"))
      (node (ref "U1") (pin "33") (pinfunction "PC4_33") (pintype "passive"))
    )
    (net (code "9") (name "/EN31") (class "Default")
      (node (ref "R13") (pin "2") (pinfunction "2_2") (pintype "passive"))
      (node (ref "U1") (pin "36") (pinfunction "PB1_36") (pintype "passive"))
    )
    (net (code "10") (name "/EN32") (class "Default")
      (node (ref "R14") (pin "2") (pinfunction "2_2") (pintype "passive"))
      (node (ref "U1") (pin "38") (pinfunction "PE7_38") (pintype "passive"))
    )
    (net (code "11") (name "/EN41") (class "Default")
      (node (ref "R19") (pin "2") (pinfunction "2_2") (pintype "passive"))
      (node (ref "U1") (pin "92") (pinfunction "PB6_92") (pintype "passive"))
    )
    (net (code "12") (name "/EN42") (class "Default")
      (node (ref "R20") (pin "2") (pinfunction "2_2") (pintype "passive"))
      (node (ref "U1") (pin "91") (pinfunction "PB5_91") (pintype "passive"))
    )
    (net (code "13") (name "/EN51") (class "Default")
      (node (ref "R25") (pin "2") (pinfunction "2_2") (pintype "passive"))
      (node (ref "U1") (pin "87") (pinfunction "PD6_87") (pintype "passive"))
    )
    (net (code "14") (name "/EN52") (class "Default")
      (node (ref "R26") (pin "2") (pinfunction "2_2") (pintype "passive"))
      (node (ref "U1") (pin "86") (pinfunction "PD5_86") (pintype "passive"))
    )
    (net (code "15") (name "/LED1") (class "Default")
      (node (ref "D23") (pin "1") (pinfunction "A_1") (pintype "passive"))
      (node (ref "U1") (pin "1") (pinfunction "PE2_1") (pintype "passive"))
    )
    (net (code "16") (name "/LED2") (class "Default")
      (node (ref "D24") (pin "1") (pinfunction "A_1") (pintype "passive"))
      (node (ref "U1") (pin "2") (pinfunction "PE3_2") (pintype "passive"))
    )
    (net (code "17") (name "/OSC_IN") (class "Default")
      (node (ref "C13") (pin "1") (pinfunction "1_1") (pintype "passive"))
      (node (ref "U1") (pin "12") (pinfunction "PH0_12") (pintype "passive"))
      (node (ref "Y1") (pin "1") (pinfunction "CRYSTAL_1_1") (pintype "passive"))
    )
    (net (code "18") (name "/OSC_OUT") (class "Default")
      (node (ref "C14") (pin "1") (pinfunction "1_1") (pintype "passive"))
      (node (ref "U1") (pin "13") (pinfunction "PH1_13") (pintype "passive"))
      (node (ref "Y1") (pin "3") (pinfunction "CRYSTAL_2_3") (pintype "passive"))
    )
    (net (code "19") (name "/OUT11") (class "Default")
      (node (ref "P3") (pin "1") (pinfunction "1_1") (pintype "passive"))
      (node (ref "Relay1") (pin "1") (pinfunction "OUT1_1") (pintype "passive"))
    )
    (net (code "20") (name "/OUT12") (class "Default")
      (node (ref "P8") (pin "1") (pinfunction "1_1") (pintype "passive"))
      (node (ref "Relay2") (pin "1") (pinfunction "OUT1_1") (pintype "passive"))
    )
    (net (code "21") (name "/OUT21") (class "Default")
      (node (ref "P4") (pin "1") (pinfunction "1_1") (pintype "passive"))
      (node (ref "Relay3") (pin "1") (pinfunction "OUT1_1") (pintype "passive"))
    )
    (net (code "22") (name "/OUT22") (class "Default")
      (node (ref "P9") (pin "1") (pinfunction "1_1") (pintype "passive"))
      (node (ref "Relay4") (pin "1") (pinfunction "OUT1_1") (pintype "passive"))
    )
    (net (code "23") (name "/OUT31") (class "Default")
      (node (ref "P5") (pin "1") (pinfunction "1_1") (pintype "passive"))
      (node (ref "Relay5") (pin "1") (pinfunction "OUT1_1") (pintype "passive"))
    )
    (net (code "24") (name "/OUT32") (class "Default")
      (node (ref "P10") (pin "1") (pinfunction "1_1") (pintype "passive"))
      (node (ref "Relay6") (pin "1") (pinfunction "OUT1_1") (pintype "passive"))
    )
    (net (code "25") (name "/OUT41") (class "Default")
      (node (ref "P6") (pin "1") (pinfunction "1_1") (pintype "passive"))
      (node (ref "Relay7") (pin "1") (pinfunction "OUT1_1") (pintype "passive"))
    )
    (net (code "26") (name "/OUT42") (class "Default")
      (node (ref "P11") (pin "1") (pinfunction "1_1") (pintype "passive"))
      (node (ref "Relay8") (pin "1") (pinfunction "OUT1_1") (pintype "passive"))
    )
    (net (code "27") (name "/OUT51") (class "Default")
      (node (ref "P7") (pin "1") (pinfunction "1_1") (pintype "passive"))
      (node (ref "Relay9") (pin "1") (pinfunction "OUT1_1") (pintype "passive"))
    )
    (net (code "28") (name "/OUT52") (class "Default")
      (node (ref "P12") (pin "1") (pinfunction "1_1") (pintype "passive"))
      (node (ref "Relay10") (pin "1") (pinfunction "OUT1_1") (pintype "passive"))
    )
    (net (code "29") (name "/RESET") (class "Default")
      (node (ref "C2") (pin "2") (pinfunction "2_2") (pintype "passive"))
      (node (ref "K1") (pin "2") (pinfunction "2_2") (pintype "passive"))
      (node (ref "R32") (pin "1") (pinfunction "1_1") (pintype "passive"))
      (node (ref "U1") (pin "14") (pinfunction "NRST_14") (pintype "input"))
    )
    (net (code "30") (name "/SWCLK") (class "Default")
      (node (ref "P13") (pin "1") (pinfunction "1_1") (pintype "passive"))
      (node (ref "U1") (pin "76") (pinfunction "PA14_76") (pintype "passive"))
    )
    (net (code "31") (name "/SWDIO") (class "Default")
      (node (ref "P13") (pin "3") (pinfunction "3_3") (pintype "passive"))
      (node (ref "U1") (pin "72") (pinfunction "PA13_72") (pintype "passive"))
    )
    (net (code "32") (name "/Signal1") (class "Default")
      (node (ref "P3") (pin "2") (pinfunction "2_2") (pintype "passive"))
      (node (ref "U1") (pin "16") (pinfunction "PC1_16") (pintype "passive"))
    )
    (net (code "33") (name "/Signal2") (class "Default")
      (node (ref "P4") (pin "2") (pinfunction "2_2") (pintype "passive"))
      (node (ref "U1") (pin "32") (pinfunction "PA7_32") (pintype "passive"))
    )
    (net (code "34") (name "/Signal3") (class "Default")
      (node (ref "P5") (pin "2") (pinfunction "2_2") (pintype "passive"))
      (node (ref "U1") (pin "35") (pinfunction "PB0_35") (pintype "passive"))
    )
    (net (code "35") (name "/Signal4") (class "Default")
      (node (ref "P6") (pin "2") (pinfunction "2_2") (pintype "passive"))
      (node (ref "U1") (pin "93") (pinfunction "PB7_93") (pintype "passive"))
    )
    (net (code "36") (name "/Signal5") (class "Default")
      (node (ref "P7") (pin "2") (pinfunction "2_2") (pintype "passive"))
      (node (ref "U1") (pin "88") (pinfunction "PD7_88") (pintype "passive"))
    )
    (net (code "37") (name "/USART6_RX") (class "Default")
      (node (ref "P1") (pin "1") (pinfunction "1_1") (pintype "passive"))
      (node (ref "U1") (pin "64") (pinfunction "PC7_64") (pintype "passive"))
    )
    (net (code "38") (name "/USART6_TX") (class "Default")
      (node (ref "P1") (pin "2") (pinfunction "2_2") (pintype "passive"))
      (node (ref "U1") (pin "63") (pinfunction "PC6_63") (pintype "passive"))
    )
    (net (code "39") (name "3V3") (class "Default")
      (node (ref "C1") (pin "2") (pinfunction "2_2") (pintype "passive"))
      (node (ref "C10") (pin "2") (pinfunction "2_2") (pintype "passive"))
      (node (ref "C11") (pin "2") (pinfunction "2_2") (pintype "passive"))
      (node (ref "C12") (pin "2") (pinfunction "2_2") (pintype "passive"))
      (node (ref "C4") (pin "2") (pinfunction "2_2") (pintype "passive"))
      (node (ref "C5") (pin "2") (pinfunction "2_2") (pintype "passive"))
      (node (ref "C6") (pin "2") (pinfunction "2_2") (pintype "passive"))
      (node (ref "C7") (pin "2") (pinfunction "2_2") (pintype "passive"))
      (node (ref "C8") (pin "2") (pinfunction "2_2") (pintype "passive"))
      (node (ref "C9") (pin "2") (pinfunction "2_2") (pintype "passive"))
      (node (ref "CAN？") (pin "3") (pinfunction "VCC_3") (pintype "power_in"))
      (node (ref "D22") (pin "1") (pinfunction "A_1") (pintype "passive"))
      (node (ref "LDO1") (pin "2") (pinfunction "OUT_2") (pintype "power_in"))
      (node (ref "LDO1") (pin "4") (pinfunction "OUT_4") (pintype "power_in"))
      (node (ref "P1") (pin "4") (pinfunction "4_4") (pintype "passive"))
      (node (ref "P13") (pin "4") (pinfunction "4_4") (pintype "passive"))
      (node (ref "R32") (pin "2") (pinfunction "2_2") (pintype "passive"))
      (node (ref "U1") (pin "100") (pinfunction "VDD_6_100") (pintype "power_in"))
      (node (ref "U1") (pin "11") (pinfunction "VDD_1_11") (pintype "power_in"))
      (node (ref "U1") (pin "19") (pinfunction "VDD_2_19") (pintype "power_in"))
      (node (ref "U1") (pin "21") (pinfunction "VREF+_21") (pintype "input"))
      (node (ref "U1") (pin "22") (pinfunction "VDDA_22") (pintype "power_in"))
      (node (ref "U1") (pin "28") (pinfunction "VDD_3_28") (pintype "power_in"))
      (node (ref "U1") (pin "50") (pinfunction "VDD_4_50") (pintype "power_in"))
      (node (ref "U1") (pin "6") (pinfunction "VBAT_6") (pintype "passive"))
      (node (ref "U1") (pin "75") (pinfunction "VDD_5_75") (pintype "power_in"))
    )
    (net (code "40") (name "5V") (class "Default")
      (node (ref "C17") (pin "1") (pinfunction "1_1") (pintype "passive"))
      (node (ref "L1") (pin "2") (pinfunction "2_2") (pintype "passive"))
      (node (ref "LDO1") (pin "3") (pinfunction "IN_3") (pintype "power_in"))
      (node (ref "R35") (pin "2") (pinfunction "2_2") (pintype "passive"))
    )
    (net (code "41") (name "24V") (class "Default")
      (node (ref "*") (pin "2") (pinfunction "VIN_2") (pintype "power_in"))
      (node (ref "*") (pin "3") (pinfunction "EN_3") (pintype "power_in"))
      (node (ref "C18") (pin "1") (pinfunction "1_1") (pintype "passive"))
      (node (ref "D11") (pin "2") (pinfunction "K_2") (pintype "passive"))
      (node (ref "D12") (pin "2") (pinfunction "K_2") (pintype "passive"))
      (node (ref "D15") (pin "2") (pinfunction "K_2") (pintype "passive"))
      (node (ref "D16") (pin "2") (pinfunction "K_2") (pintype "passive"))
      (node (ref "D19") (pin "2") (pinfunction "K_2") (pintype "passive"))
      (node (ref "D20") (pin "2") (pinfunction "K_2") (pintype "passive"))
      (node (ref "D3") (pin "2") (pinfunction "K_2") (pintype "passive"))
      (node (ref "D4") (pin "2") (pinfunction "K_2") (pintype "passive"))
      (node (ref "D7") (pin "2") (pinfunction "K_2") (pintype "passive"))
      (node (ref "D8") (pin "2") (pinfunction "K_2") (pintype "passive"))
      (node (ref "PI1") (pin "1") (pinfunction "VCC_1") (pintype "passive"))
      (node (ref "PI2") (pin "1") (pinfunction "VCC_1") (pintype "passive"))
      (node (ref "Relay1") (pin "4") (pinfunction "VCC2_4") (pintype "passive"))
      (node (ref "Relay1") (pin "5") (pinfunction "INT_5") (pintype "passive"))
      (node (ref "Relay10") (pin "4") (pinfunction "VCC2_4") (pintype "passive"))
      (node (ref "Relay10") (pin "5") (pinfunction "INT_5") (pintype "passive"))
      (node (ref "Relay2") (pin "4") (pinfunction "VCC2_4") (pintype "passive"))
      (node (ref "Relay2") (pin "5") (pinfunction "INT_5") (pintype "passive"))
      (node (ref "Relay3") (pin "4") (pinfunction "VCC2_4") (pintype "passive"))
      (node (ref "Relay3") (pin "5") (pinfunction "INT_5") (pintype "passive"))
      (node (ref "Relay4") (pin "4") (pinfunction "VCC2_4") (pintype "passive"))
      (node (ref "Relay4") (pin "5") (pinfunction "INT_5") (pintype "passive"))
      (node (ref "Relay5") (pin "4") (pinfunction "VCC2_4") (pintype "passive"))
      (node (ref "Relay5") (pin "5") (pinfunction "INT_5") (pintype "passive"))
      (node (ref "Relay6") (pin "4") (pinfunction "VCC2_4") (pintype "passive"))
      (node (ref "Relay6") (pin "5") (pinfunction "INT_5") (pintype "passive"))
      (node (ref "Relay7") (pin "4") (pinfunction "VCC2_4") (pintype "passive"))
      (node (ref "Relay7") (pin "5") (pinfunction "INT_5") (pintype "passive"))
      (node (ref "Relay8") (pin "4") (pinfunction "VCC2_4") (pintype "passive"))
      (node (ref "Relay8") (pin "5") (pinfunction "INT_5") (pintype "passive"))
      (node (ref "Relay9") (pin "4") (pinfunction "VCC2_4") (pintype "passive"))
      (node (ref "Relay9") (pin "5") (pinfunction "INT_5") (pintype "passive"))
    )
    (net (code "42") (name "DGND") (class "Default")
      (node (ref "C10") (pin "1") (pinfunction "1_1") (pintype "passive"))
      (node (ref "C11") (pin "1") (pinfunction "1_1") (pintype "passive"))
      (node (ref "C12") (pin "1") (pinfunction "1_1") (pintype "passive"))
      (node (ref "C13") (pin "2") (pinfunction "2_2") (pintype "passive"))
      (node (ref "C14") (pin "2") (pinfunction "2_2") (pintype "passive"))
      (node (ref "C15") (pin "1") (pinfunction "1_1") (pintype "passive"))
      (node (ref "C2") (pin "1") (pinfunction "1_1") (pintype "passive"))
      (node (ref "C3") (pin "2") (pinfunction "2_2") (pintype "passive"))
      (node (ref "C4") (pin "1") (pinfunction "1_1") (pintype "passive"))
      (node (ref "C5") (pin "1") (pinfunction "1_1") (pintype "passive"))
      (node (ref "C6") (pin "1") (pinfunction "1_1") (pintype "passive"))
      (node (ref "C7") (pin "1") (pinfunction "1_1") (pintype "passive"))
      (node (ref "C8") (pin "1") (pinfunction "1_1") (pintype "passive"))
      (node (ref "C9") (pin "1") (pinfunction "1_1") (pintype "passive"))
      (node (ref "CAN？") (pin "2") (pinfunction "GND_2") (pintype "power_in"))
      (node (ref "K1") (pin "1") (pinfunction "1_1") (pintype "passive"))
      (node (ref "P1") (pin "3") (pinfunction "3_3") (pintype "passive"))
      (node (ref "P13") (pin "2") (pinfunction "2_2") (pintype "passive"))
      (node (ref "R31") (pin "2") (pinfunction "2_2") (pintype "passive"))
      (node (ref "R33") (pin "1") (pinfunction "1_1") (pintype "passive"))
      (node (ref "R39") (pin "2") (pinfunction "2_2") (pintype "passive"))
      (node (ref "R40") (pin "2") (pinfunction "2_2") (pintype "passive"))
      (node (ref "R42") (pin "2") (pinfunction "2_2") (pintype "passive"))
      (node (ref "R43") (pin "2") (pinfunction "2_2") (pintype "passive"))
      (node (ref "U1") (pin "10") (pinfunction "VSS_1_10") (pintype "power_in"))
      (node (ref "U1") (pin "20") (pinfunction "VSSA_20") (pintype "power_in"))
      (node (ref "U1") (pin "27") (pinfunction "VSS_2_27") (pintype "power_in"))
      (node (ref "U1") (pin "74") (pinfunction "VSS_3_74") (pintype "power_in"))
      (node (ref "U1") (pin "99") (pinfunction "VSS_4_99") (pintype "power_in"))
      (node (ref "Y1") (pin "2") (pinfunction "GND_1_2") (pintype "passive"))
      (node (ref "Y1") (pin "4") (pinfunction "GND_2_4") (pintype "passive"))
    )
    (net (code "43") (name "GND") (class "Default")
      (node (ref "*") (pin "7") (pinfunction "GND_7") (pintype "power_in"))
      (node (ref "*") (pin "9") (pinfunction "PGND_9") (pintype "power_in"))
      (node (ref "C1") (pin "1") (pinfunction "1_1") (pintype "passive"))
      (node (ref "C17") (pin "2") (pinfunction "2_2") (pintype "passive"))
      (node (ref "C18") (pin "2") (pinfunction "2_2") (pintype "passive"))
      (node (ref "C19") (pin "2") (pinfunction "2_2") (pintype "passive"))
      (node (ref "D21") (pin "1") (pinfunction "A_1") (pintype "passive"))
      (node (ref "LDO1") (pin "1") (pinfunction "GND_1") (pintype "power_in"))
      (node (ref "P10") (pin "2") (pinfunction "2_2") (pintype "passive"))
      (node (ref "P11") (pin "2") (pinfunction "2_2") (pintype "passive"))
      (node (ref "P12") (pin "2") (pinfunction "2_2") (pintype "passive"))
      (node (ref "P3") (pin "3") (pinfunction "3_3") (pintype "passive"))
      (node (ref "P4") (pin "3") (pinfunction "3_3") (pintype "passive"))
      (node (ref "P5") (pin "3") (pinfunction "3_3") (pintype "passive"))
      (node (ref "P6") (pin "3") (pinfunction "3_3") (pintype "passive"))
      (node (ref "P7") (pin "3") (pinfunction "3_3") (pintype "passive"))
      (node (ref "P8") (pin "2") (pinfunction "2_2") (pintype "passive"))
      (node (ref "P9") (pin "2") (pinfunction "2_2") (pintype "passive"))
      (node (ref "PI1") (pin "2") (pinfunction "GND_2") (pintype "passive"))
      (node (ref "PI2") (pin "2") (pinfunction "GND_2") (pintype "passive"))
      (node (ref "Q1") (pin "3") (pinfunction "E_3") (pintype "passive"))
      (node (ref "Q10") (pin "3") (pinfunction "E_3") (pintype "passive"))
      (node (ref "Q2") (pin "3") (pinfunction "E_3") (pintype "passive"))
      (node (ref "Q3") (pin "3") (pinfunction "E_3") (pintype "passive"))
      (node (ref "Q4") (pin "3") (pinfunction "E_3") (pintype "passive"))
      (node (ref "Q5") (pin "3") (pinfunction "E_3") (pintype "passive"))
      (node (ref "Q6") (pin "3") (pinfunction "E_3") (pintype "passive"))
      (node (ref "Q7") (pin "3") (pinfunction "E_3") (pintype "passive"))
      (node (ref "Q8") (pin "3") (pinfunction "E_3") (pintype "passive"))
      (node (ref "Q9") (pin "3") (pinfunction "E_3") (pintype "passive"))
      (node (ref "R11") (pin "1") (pinfunction "1_1") (pintype "passive"))
      (node (ref "R15") (pin "1") (pinfunction "1_1") (pintype "passive"))
      (node (ref "R17") (pin "1") (pinfunction "1_1") (pintype "passive"))
      (node (ref "R21") (pin "1") (pinfunction "1_1") (pintype "passive"))
      (node (ref "R23") (pin "1") (pinfunction "1_1") (pintype "passive"))
      (node (ref "R27") (pin "1") (pinfunction "1_1") (pintype "passive"))
      (node (ref "R29") (pin "1") (pinfunction "1_1") (pintype "passive"))
      (node (ref "R3") (pin "1") (pinfunction "1_1") (pintype "passive"))
      (node (ref "R37") (pin "1") (pinfunction "1_1") (pintype "passive"))
      (node (ref "R38") (pin "1") (pinfunction "1_1") (pintype "passive"))
      (node (ref "R43") (pin "1") (pinfunction "1_1") (pintype "passive"))
      (node (ref "R5") (pin "1") (pinfunction "1_1") (pintype "passive"))
      (node (ref "R9") (pin "1") (pinfunction "1_1") (pintype "passive"))
    )
    (net (code "44") (name "Net-(*-BOOT)") (class "Default")
      (node (ref "*") (pin "1") (pinfunction "BOOT_1") (pintype "power_in"))
      (node (ref "C16") (pin "1") (pinfunction "1_1") (pintype "passive"))
    )
    (net (code "45") (name "Net-(*-FB)") (class "Default")
      (node (ref "*") (pin "5") (pinfunction "FB_5") (pintype "power_in"))
      (node (ref "R35") (pin "1") (pinfunction "1_1") (pintype "passive"))
      (node (ref "R38") (pin "2") (pinfunction "2_2") (pintype "passive"))
    )
    (net (code "46") (name "Net-(*-RT{slash}SYNC)") (class "Default")
      (node (ref "*") (pin "4") (pinfunction "RT/SYNC_4") (pintype "power_in"))
      (node (ref "R37") (pin "2") (pinfunction "2_2") (pintype "passive"))
    )
    (net (code "47") (name "Net-(*-SS)") (class "Default")
      (node (ref "*") (pin "6") (pinfunction "SS_6") (pintype "power_in"))
      (node (ref "C19") (pin "1") (pinfunction "1_1") (pintype "passive"))
    )
    (net (code "48") (name "Net-(*-SW)") (class "Default")
      (node (ref "*") (pin "8") (pinfunction "SW_8") (pintype "power_in"))
      (node (ref "C16") (pin "2") (pinfunction "2_2") (pintype "passive"))
      (node (ref "D21") (pin "2") (pinfunction "K_2") (pintype "passive"))
      (node (ref "L1") (pin "1") (pinfunction "1_1") (pintype "passive"))
    )
    (net (code "49") (name "Net-(D1-A)") (class "Default")
      (node (ref "D1") (pin "1") (pinfunction "A_1") (pintype "passive"))
      (node (ref "Relay1") (pin "3") (pinfunction "VCC1_3") (pintype "passive"))
    )
    (net (code "50") (name "Net-(D1-K)") (class "Default")
      (node (ref "D1") (pin "2") (pinfunction "K_2") (pintype "passive"))
      (node (ref "R4") (pin "2") (pinfunction "2_2") (pintype "passive"))
    )
    (net (code "51") (name "Net-(D2-A)") (class "Default")
      (node (ref "D2") (pin "1") (pinfunction "A_1") (pintype "passive"))
      (node (ref "Relay2") (pin "3") (pinfunction "VCC1_3") (pintype "passive"))
    )
    (net (code "52") (name "Net-(D2-K)") (class "Default")
      (node (ref "D2") (pin "2") (pinfunction "K_2") (pintype "passive"))
      (node (ref "R6") (pin "2") (pinfunction "2_2") (pintype "passive"))
    )
    (net (code "53") (name "Net-(D3-A)") (class "Default")
      (node (ref "D3") (pin "1") (pinfunction "A_1") (pintype "passive"))
      (node (ref "Q1") (pin "1") (pinfunction "C_1") (pintype "passive"))
      (node (ref "R4") (pin "1") (pinfunction "1_1") (pintype "passive"))
    )
    (net (code "54") (name "Net-(D4-A)") (class "Default")
      (node (ref "D4") (pin "1") (pinfunction "A_1") (pintype "passive"))
      (node (ref "Q2") (pin "1") (pinfunction "C_1") (pintype "passive"))
      (node (ref "R6") (pin "1") (pinfunction "1_1") (pintype "passive"))
    )
    (net (code "55") (name "Net-(D5-A)") (class "Default")
      (node (ref "D5") (pin "1") (pinfunction "A_1") (pintype "passive"))
      (node (ref "Relay3") (pin "3") (pinfunction "VCC1_3") (pintype "passive"))
    )
    (net (code "56") (name "Net-(D5-K)") (class "Default")
      (node (ref "D5") (pin "2") (pinfunction "K_2") (pintype "passive"))
      (node (ref "R10") (pin "2") (pinfunction "2_2") (pintype "passive"))
    )
    (net (code "57") (name "Net-(D6-A)") (class "Default")
      (node (ref "D6") (pin "1") (pinfunction "A_1") (pintype "passive"))
      (node (ref "Relay4") (pin "3") (pinfunction "VCC1_3") (pintype "passive"))
    )
    (net (code "58") (name "Net-(D6-K)") (class "Default")
      (node (ref "D6") (pin "2") (pinfunction "K_2") (pintype "passive"))
      (node (ref "R12") (pin "2") (pinfunction "2_2") (pintype "passive"))
    )
    (net (code "59") (name "Net-(D7-A)") (class "Default")
      (node (ref "D7") (pin "1") (pinfunction "A_1") (pintype "passive"))
      (node (ref "Q3") (pin "1") (pinfunction "C_1") (pintype "passive"))
      (node (ref "R10") (pin "1") (pinfunction "1_1") (pintype "passive"))
    )
    (net (code "60") (name "Net-(D8-A)") (class "Default")
      (node (ref "D8") (pin "1") (pinfunction "A_1") (pintype "passive"))
      (node (ref "Q4") (pin "1") (pinfunction "C_1") (pintype "passive"))
      (node (ref "R12") (pin "1") (pinfunction "1_1") (pintype "passive"))
    )
    (net (code "61") (name "Net-(D9-A)") (class "Default")
      (node (ref "D9") (pin "1") (pinfunction "A_1") (pintype "passive"))
      (node (ref "Relay5") (pin "3") (pinfunction "VCC1_3") (pintype "passive"))
    )
    (net (code "62") (name "Net-(D9-K)") (class "Default")
      (node (ref "D9") (pin "2") (pinfunction "K_2") (pintype "passive"))
      (node (ref "R16") (pin "2") (pinfunction "2_2") (pintype "passive"))
    )
    (net (code "63") (name "Net-(D10-A)") (class "Default")
      (node (ref "D10") (pin "1") (pinfunction "A_1") (pintype "passive"))
      (node (ref "Relay6") (pin "3") (pinfunction "VCC1_3") (pintype "passive"))
    )
    (net (code "64") (name "Net-(D10-K)") (class "Default")
      (node (ref "D10") (pin "2") (pinfunction "K_2") (pintype "passive"))
      (node (ref "R18") (pin "2") (pinfunction "2_2") (pintype "passive"))
    )
    (net (code "65") (name "Net-(D11-A)") (class "Default")
      (node (ref "D11") (pin "1") (pinfunction "A_1") (pintype "passive"))
      (node (ref "Q5") (pin "1") (pinfunction "C_1") (pintype "passive"))
      (node (ref "R16") (pin "1") (pinfunction "1_1") (pintype "passive"))
    )
    (net (code "66") (name "Net-(D12-A)") (class "Default")
      (node (ref "D12") (pin "1") (pinfunction "A_1") (pintype "passive"))
      (node (ref "Q6") (pin "1") (pinfunction "C_1") (pintype "passive"))
      (node (ref "R18") (pin "1") (pinfunction "1_1") (pintype "passive"))
    )
    (net (code "67") (name "Net-(D13-A)") (class "Default")
      (node (ref "D13") (pin "1") (pinfunction "A_1") (pintype "passive"))
      (node (ref "Relay7") (pin "3") (pinfunction "VCC1_3") (pintype "passive"))
    )
    (net (code "68") (name "Net-(D13-K)") (class "Default")
      (node (ref "D13") (pin "2") (pinfunction "K_2") (pintype "passive"))
      (node (ref "R22") (pin "2") (pinfunction "2_2") (pintype "passive"))
    )
    (net (code "69") (name "Net-(D14-A)") (class "Default")
      (node (ref "D14") (pin "1") (pinfunction "A_1") (pintype "passive"))
      (node (ref "Relay8") (pin "3") (pinfunction "VCC1_3") (pintype "passive"))
    )
    (net (code "70") (name "Net-(D14-K)") (class "Default")
      (node (ref "D14") (pin "2") (pinfunction "K_2") (pintype "passive"))
      (node (ref "R24") (pin "2") (pinfunction "2_2") (pintype "passive"))
    )
    (net (code "71") (name "Net-(D15-A)") (class "Default")
      (node (ref "D15") (pin "1") (pinfunction "A_1") (pintype "passive"))
      (node (ref "Q7") (pin "1") (pinfunction "C_1") (pintype "passive"))
      (node (ref "R22") (pin "1") (pinfunction "1_1") (pintype "passive"))
    )
    (net (code "72") (name "Net-(D16-A)") (class "Default")
      (node (ref "D16") (pin "1") (pinfunction "A_1") (pintype "passive"))
      (node (ref "Q8") (pin "1") (pinfunction "C_1") (pintype "passive"))
      (node (ref "R24") (pin "1") (pinfunction "1_1") (pintype "passive"))
    )
    (net (code "73") (name "Net-(D17-A)") (class "Default")
      (node (ref "D17") (pin "1") (pinfunction "A_1") (pintype "passive"))
      (node (ref "Relay9") (pin "3") (pinfunction "VCC1_3") (pintype "passive"))
    )
    (net (code "74") (name "Net-(D17-K)") (class "Default")
      (node (ref "D17") (pin "2") (pinfunction "K_2") (pintype "passive"))
      (node (ref "R28") (pin "2") (pinfunction "2_2") (pintype "passive"))
    )
    (net (code "75") (name "Net-(D18-A)") (class "Default")
      (node (ref "D18") (pin "1") (pinfunction "A_1") (pintype "passive"))
      (node (ref "Relay10") (pin "3") (pinfunction "VCC1_3") (pintype "passive"))
    )
    (net (code "76") (name "Net-(D18-K)") (class "Default")
      (node (ref "D18") (pin "2") (pinfunction "K_2") (pintype "passive"))
      (node (ref "R30") (pin "2") (pinfunction "2_2") (pintype "passive"))
    )
    (net (code "77") (name "Net-(D19-A)") (class "Default")
      (node (ref "D19") (pin "1") (pinfunction "A_1") (pintype "passive"))
      (node (ref "Q9") (pin "1") (pinfunction "C_1") (pintype "passive"))
      (node (ref "R28") (pin "1") (pinfunction "1_1") (pintype "passive"))
    )
    (net (code "78") (name "Net-(D20-A)") (class "Default")
      (node (ref "D20") (pin "1") (pinfunction "A_1") (pintype "passive"))
      (node (ref "Q10") (pin "1") (pinfunction "C_1") (pintype "passive"))
      (node (ref "R30") (pin "1") (pinfunction "1_1") (pintype "passive"))
    )
    (net (code "79") (name "Net-(D22-K)") (class "Default")
      (node (ref "D22") (pin "2") (pinfunction "K_2") (pintype "passive"))
      (node (ref "R39") (pin "1") (pinfunction "1_1") (pintype "passive"))
    )
    (net (code "80") (name "Net-(D23-K)") (class "Default")
      (node (ref "D23") (pin "2") (pinfunction "K_2") (pintype "passive"))
      (node (ref "R40") (pin "1") (pinfunction "1_1") (pintype "passive"))
    )
    (net (code "81") (name "Net-(D24-K)") (class "Default")
      (node (ref "D24") (pin "2") (pinfunction "K_2") (pintype "passive"))
      (node (ref "R42") (pin "1") (pinfunction "1_1") (pintype "passive"))
    )
    (net (code "82") (name "Net-(Q1-B)") (class "Default")
      (node (ref "Q1") (pin "2") (pinfunction "B_2") (pintype "passive"))
      (node (ref "R1") (pin "1") (pinfunction "1_1") (pintype "passive"))
      (node (ref "R3") (pin "2") (pinfunction "2_2") (pintype "passive"))
    )
    (net (code "83") (name "Net-(Q2-B)") (class "Default")
      (node (ref "Q2") (pin "2") (pinfunction "B_2") (pintype "passive"))
      (node (ref "R2") (pin "1") (pinfunction "1_1") (pintype "passive"))
      (node (ref "R5") (pin "2") (pinfunction "2_2") (pintype "passive"))
    )
    (net (code "84") (name "Net-(Q3-B)") (class "Default")
      (node (ref "Q3") (pin "2") (pinfunction "B_2") (pintype "passive"))
      (node (ref "R7") (pin "1") (pinfunction "1_1") (pintype "passive"))
      (node (ref "R9") (pin "2") (pinfunction "2_2") (pintype "passive"))
    )
    (net (code "85") (name "Net-(Q4-B)") (class "Default")
      (node (ref "Q4") (pin "2") (pinfunction "B_2") (pintype "passive"))
      (node (ref "R11") (pin "2") (pinfunction "2_2") (pintype "passive"))
      (node (ref "R8") (pin "1") (pinfunction "1_1") (pintype "passive"))
    )
    (net (code "86") (name "Net-(Q5-B)") (class "Default")
      (node (ref "Q5") (pin "2") (pinfunction "B_2") (pintype "passive"))
      (node (ref "R13") (pin "1") (pinfunction "1_1") (pintype "passive"))
      (node (ref "R15") (pin "2") (pinfunction "2_2") (pintype "passive"))
    )
    (net (code "87") (name "Net-(Q6-B)") (class "Default")
      (node (ref "Q6") (pin "2") (pinfunction "B_2") (pintype "passive"))
      (node (ref "R14") (pin "1") (pinfunction "1_1") (pintype "passive"))
      (node (ref "R17") (pin "2") (pinfunction "2_2") (pintype "passive"))
    )
    (net (code "88") (name "Net-(Q7-B)") (class "Default")
      (node (ref "Q7") (pin "2") (pinfunction "B_2") (pintype "passive"))
      (node (ref "R19") (pin "1") (pinfunction "1_1") (pintype "passive"))
      (node (ref "R21") (pin "2") (pinfunction "2_2") (pintype "passive"))
    )
    (net (code "89") (name "Net-(Q8-B)") (class "Default")
      (node (ref "Q8") (pin "2") (pinfunction "B_2") (pintype "passive"))
      (node (ref "R20") (pin "1") (pinfunction "1_1") (pintype "passive"))
      (node (ref "R23") (pin "2") (pinfunction "2_2") (pintype "passive"))
    )
    (net (code "90") (name "Net-(Q9-B)") (class "Default")
      (node (ref "Q9") (pin "2") (pinfunction "B_2") (pintype "passive"))
      (node (ref "R25") (pin "1") (pinfunction "1_1") (pintype "passive"))
      (node (ref "R27") (pin "2") (pinfunction "2_2") (pintype "passive"))
    )
    (net (code "91") (name "Net-(Q10-B)") (class "Default")
      (node (ref "Q10") (pin "2") (pinfunction "B_2") (pintype "passive"))
      (node (ref "R26") (pin "1") (pinfunction "1_1") (pintype "passive"))
      (node (ref "R29") (pin "2") (pinfunction "2_2") (pintype "passive"))
    )
    (net (code "92") (name "Net-(U1-BOOT0)") (class "Default")
      (node (ref "R31") (pin "1") (pinfunction "1_1") (pintype "passive"))
      (node (ref "U1") (pin "94") (pinfunction "BOOT0_94") (pintype "passive"))
    )
    (net (code "93") (name "Net-(U1-PB2)") (class "Default")
      (node (ref "R33") (pin "2") (pinfunction "2_2") (pintype "passive"))
      (node (ref "U1") (pin "37") (pinfunction "PB2_37") (pintype "passive"))
    )
    (net (code "94") (name "Net-(U1-VCAP_1)") (class "Default")
      (node (ref "C15") (pin "2") (pinfunction "2_2") (pintype "passive"))
      (node (ref "U1") (pin "49") (pinfunction "VCAP_1_49") (pintype "passive"))
    )
    (net (code "95") (name "Net-(U1-VCAP_2)") (class "Default")
      (node (ref "C3") (pin "1") (pinfunction "1_1") (pintype "passive"))
      (node (ref "U1") (pin "73") (pinfunction "VCAP_2_73") (pintype "passive"))
    )
    (net (code "96") (name "unconnected-(CAN？-NC-Pad5)") (class "Default")
      (node (ref "CAN？") (pin "5") (pinfunction "NC_5") (pintype "power_in"))
    )
    (net (code "97") (name "unconnected-(CAN？-NC-Pad8)") (class "Default")
      (node (ref "CAN？") (pin "8") (pinfunction "NC_8") (pintype "power_in"))
    )
    (net (code "98") (name "unconnected-(Relay1-OUT2-Pad2)") (class "Default")
      (node (ref "Relay1") (pin "2") (pinfunction "OUT2_2") (pintype "passive"))
    )
    (net (code "99") (name "unconnected-(Relay2-OUT2-Pad2)") (class "Default")
      (node (ref "Relay2") (pin "2") (pinfunction "OUT2_2") (pintype "passive"))
    )
    (net (code "100") (name "unconnected-(Relay3-OUT2-Pad2)") (class "Default")
      (node (ref "Relay3") (pin "2") (pinfunction "OUT2_2") (pintype "passive"))
    )
    (net (code "101") (name "unconnected-(Relay4-OUT2-Pad2)") (class "Default")
      (node (ref "Relay4") (pin "2") (pinfunction "OUT2_2") (pintype "passive"))
    )
    (net (code "102") (name "unconnected-(Relay5-OUT2-Pad2)") (class "Default")
      (node (ref "Relay5") (pin "2") (pinfunction "OUT2_2") (pintype "passive"))
    )
    (net (code "103") (name "unconnected-(Relay6-OUT2-Pad2)") (class "Default")
      (node (ref "Relay6") (pin "2") (pinfunction "OUT2_2") (pintype "passive"))
    )
    (net (code "104") (name "unconnected-(Relay7-OUT2-Pad2)") (class "Default")
      (node (ref "Relay7") (pin "2") (pinfunction "OUT2_2") (pintype "passive"))
    )
    (net (code "105") (name "unconnected-(Relay8-OUT2-Pad2)") (class "Default")
      (node (ref "Relay8") (pin "2") (pinfunction "OUT2_2") (pintype "passive"))
    )
    (net (code "106") (name "unconnected-(Relay9-OUT2-Pad2)") (class "Default")
      (node (ref "Relay9") (pin "2") (pinfunction "OUT2_2") (pintype "passive"))
    )
    (net (code "107") (name "unconnected-(Relay10-OUT2-Pad2)") (class "Default")
      (node (ref "Relay10") (pin "2") (pinfunction "OUT2_2") (pintype "passive"))
    )
    (net (code "108") (name "unconnected-(U1-PA0-Pad23)") (class "Default")
      (node (ref "U1") (pin "23") (pinfunction "PA0_23") (pintype "passive"))
    )
    (net (code "109") (name "unconnected-(U1-PA1-Pad24)") (class "Default")
      (node (ref "U1") (pin "24") (pinfunction "PA1_24") (pintype "passive"))
    )
    (net (code "110") (name "unconnected-(U1-PA2-Pad25)") (class "Default")
      (node (ref "U1") (pin "25") (pinfunction "PA2_25") (pintype "passive"))
    )
    (net (code "111") (name "unconnected-(U1-PA3-Pad26)") (class "Default")
      (node (ref "U1") (pin "26") (pinfunction "PA3_26") (pintype "passive"))
    )
    (net (code "112") (name "unconnected-(U1-PA4-Pad29)") (class "Default")
      (node (ref "U1") (pin "29") (pinfunction "PA4_29") (pintype "passive"))
    )
    (net (code "113") (name "unconnected-(U1-PA5-Pad30)") (class "Default")
      (node (ref "U1") (pin "30") (pinfunction "PA5_30") (pintype "passive"))
    )
    (net (code "114") (name "unconnected-(U1-PA8-Pad67)") (class "Default")
      (node (ref "U1") (pin "67") (pinfunction "PA8_67") (pintype "passive"))
    )
    (net (code "115") (name "unconnected-(U1-PA9-Pad68)") (class "Default")
      (node (ref "U1") (pin "68") (pinfunction "PA9_68") (pintype "passive"))
    )
    (net (code "116") (name "unconnected-(U1-PA10-Pad69)") (class "Default")
      (node (ref "U1") (pin "69") (pinfunction "PA10_69") (pintype "passive"))
    )
    (net (code "117") (name "unconnected-(U1-PA15-Pad77)") (class "Default")
      (node (ref "U1") (pin "77") (pinfunction "PA15_77") (pintype "passive"))
    )
    (net (code "118") (name "unconnected-(U1-PB3-Pad89)") (class "Default")
      (node (ref "U1") (pin "89") (pinfunction "PB3_89") (pintype "passive"))
    )
    (net (code "119") (name "unconnected-(U1-PB4-Pad90)") (class "Default")
      (node (ref "U1") (pin "90") (pinfunction "PB4_90") (pintype "passive"))
    )
    (net (code "120") (name "unconnected-(U1-PB8-Pad95)") (class "Default")
      (node (ref "U1") (pin "95") (pinfunction "PB8_95") (pintype "passive"))
    )
    (net (code "121") (name "unconnected-(U1-PB9-Pad96)") (class "Default")
      (node (ref "U1") (pin "96") (pinfunction "PB9_96") (pintype "passive"))
    )
    (net (code "122") (name "unconnected-(U1-PB10-Pad47)") (class "Default")
      (node (ref "U1") (pin "47") (pinfunction "PB10_47") (pintype "passive"))
    )
    (net (code "123") (name "unconnected-(U1-PB11-Pad48)") (class "Default")
      (node (ref "U1") (pin "48") (pinfunction "PB11_48") (pintype "passive"))
    )
    (net (code "124") (name "unconnected-(U1-PB12-Pad51)") (class "Default")
      (node (ref "U1") (pin "51") (pinfunction "PB12_51") (pintype "passive"))
    )
    (net (code "125") (name "unconnected-(U1-PB13-Pad52)") (class "Default")
      (node (ref "U1") (pin "52") (pinfunction "PB13_52") (pintype "passive"))
    )
    (net (code "126") (name "unconnected-(U1-PB14-Pad53)") (class "Default")
      (node (ref "U1") (pin "53") (pinfunction "PB14_53") (pintype "passive"))
    )
    (net (code "127") (name "unconnected-(U1-PB15-Pad54)") (class "Default")
      (node (ref "U1") (pin "54") (pinfunction "PB15_54") (pintype "passive"))
    )
    (net (code "128") (name "unconnected-(U1-PC3-Pad18)") (class "Default")
      (node (ref "U1") (pin "18") (pinfunction "PC3_18") (pintype "passive"))
    )
    (net (code "129") (name "unconnected-(U1-PC5-Pad34)") (class "Default")
      (node (ref "U1") (pin "34") (pinfunction "PC5_34") (pintype "passive"))
    )
    (net (code "130") (name "unconnected-(U1-PC8-Pad65)") (class "Default")
      (node (ref "U1") (pin "65") (pinfunction "PC8_65") (pintype "passive"))
    )
    (net (code "131") (name "unconnected-(U1-PC9-Pad66)") (class "Default")
      (node (ref "U1") (pin "66") (pinfunction "PC9_66") (pintype "passive"))
    )
    (net (code "132") (name "unconnected-(U1-PC10-Pad78)") (class "Default")
      (node (ref "U1") (pin "78") (pinfunction "PC10_78") (pintype "passive"))
    )
    (net (code "133") (name "unconnected-(U1-PC11-Pad79)") (class "Default")
      (node (ref "U1") (pin "79") (pinfunction "PC11_79") (pintype "passive"))
    )
    (net (code "134") (name "unconnected-(U1-PC12-Pad80)") (class "Default")
      (node (ref "U1") (pin "80") (pinfunction "PC12_80") (pintype "passive"))
    )
    (net (code "135") (name "unconnected-(U1-PC13-Pad7)") (class "Default")
      (node (ref "U1") (pin "7") (pinfunction "PC13_7") (pintype "passive"))
    )
    (net (code "136") (name "unconnected-(U1-PC14-Pad8)") (class "Default")
      (node (ref "U1") (pin "8") (pinfunction "PC14_8") (pintype "passive"))
    )
    (net (code "137") (name "unconnected-(U1-PC15-Pad9)") (class "Default")
      (node (ref "U1") (pin "9") (pinfunction "PC15_9") (pintype "passive"))
    )
    (net (code "138") (name "unconnected-(U1-PD0-Pad81)") (class "Default")
      (node (ref "U1") (pin "81") (pinfunction "PD0_81") (pintype "passive"))
    )
    (net (code "139") (name "unconnected-(U1-PD1-Pad82)") (class "Default")
      (node (ref "U1") (pin "82") (pinfunction "PD1_82") (pintype "passive"))
    )
    (net (code "140") (name "unconnected-(U1-PD2-Pad83)") (class "Default")
      (node (ref "U1") (pin "83") (pinfunction "PD2_83") (pintype "passive"))
    )
    (net (code "141") (name "unconnected-(U1-PD3-Pad84)") (class "Default")
      (node (ref "U1") (pin "84") (pinfunction "PD3_84") (pintype "passive"))
    )
    (net (code "142") (name "unconnected-(U1-PD4-Pad85)") (class "Default")
      (node (ref "U1") (pin "85") (pinfunction "PD4_85") (pintype "passive"))
    )
    (net (code "143") (name "unconnected-(U1-PD8-Pad55)") (class "Default")
      (node (ref "U1") (pin "55") (pinfunction "PD8_55") (pintype "passive"))
    )
    (net (code "144") (name "unconnected-(U1-PD9-Pad56)") (class "Default")
      (node (ref "U1") (pin "56") (pinfunction "PD9_56") (pintype "passive"))
    )
    (net (code "145") (name "unconnected-(U1-PD10-Pad57)") (class "Default")
      (node (ref "U1") (pin "57") (pinfunction "PD10_57") (pintype "passive"))
    )
    (net (code "146") (name "unconnected-(U1-PD11-Pad58)") (class "Default")
      (node (ref "U1") (pin "58") (pinfunction "PD11_58") (pintype "passive"))
    )
    (net (code "147") (name "unconnected-(U1-PD12-Pad59)") (class "Default")
      (node (ref "U1") (pin "59") (pinfunction "PD12_59") (pintype "passive"))
    )
    (net (code "148") (name "unconnected-(U1-PD13-Pad60)") (class "Default")
      (node (ref "U1") (pin "60") (pinfunction "PD13_60") (pintype "passive"))
    )
    (net (code "149") (name "unconnected-(U1-PD14-Pad61)") (class "Default")
      (node (ref "U1") (pin "61") (pinfunction "PD14_61") (pintype "passive"))
    )
    (net (code "150") (name "unconnected-(U1-PD15-Pad62)") (class "Default")
      (node (ref "U1") (pin "62") (pinfunction "PD15_62") (pintype "passive"))
    )
    (net (code "151") (name "unconnected-(U1-PE0-Pad97)") (class "Default")
      (node (ref "U1") (pin "97") (pinfunction "PE0_97") (pintype "passive"))
    )
    (net (code "152") (name "unconnected-(U1-PE1-Pad98)") (class "Default")
      (node (ref "U1") (pin "98") (pinfunction "PE1_98") (pintype "passive"))
    )
    (net (code "153") (name "unconnected-(U1-PE4-Pad3)") (class "Default")
      (node (ref "U1") (pin "3") (pinfunction "PE4_3") (pintype "passive"))
    )
    (net (code "154") (name "unconnected-(U1-PE5-Pad4)") (class "Default")
      (node (ref "U1") (pin "4") (pinfunction "PE5_4") (pintype "passive"))
    )
    (net (code "155") (name "unconnected-(U1-PE6-Pad5)") (class "Default")
      (node (ref "U1") (pin "5") (pinfunction "PE6_5") (pintype "passive"))
    )
    (net (code "156") (name "unconnected-(U1-PE8-Pad39)") (class "Default")
      (node (ref "U1") (pin "39") (pinfunction "PE8_39") (pintype "passive"))
    )
    (net (code "157") (name "unconnected-(U1-PE9-Pad40)") (class "Default")
      (node (ref "U1") (pin "40") (pinfunction "PE9_40") (pintype "passive"))
    )
    (net (code "158") (name "unconnected-(U1-PE10-Pad41)") (class "Default")
      (node (ref "U1") (pin "41") (pinfunction "PE10_41") (pintype "passive"))
    )
    (net (code "159") (name "unconnected-(U1-PE11-Pad42)") (class "Default")
      (node (ref "U1") (pin "42") (pinfunction "PE11_42") (pintype "passive"))
    )
    (net (code "160") (name "unconnected-(U1-PE12-Pad43)") (class "Default")
      (node (ref "U1") (pin "43") (pinfunction "PE12_43") (pintype "passive"))
    )
    (net (code "161") (name "unconnected-(U1-PE13-Pad44)") (class "Default")
      (node (ref "U1") (pin "44") (pinfunction "PE13_44") (pintype "passive"))
    )
    (net (code "162") (name "unconnected-(U1-PE14-Pad45)") (class "Default")
      (node (ref "U1") (pin "45") (pinfunction "PE14_45") (pintype "passive"))
    )
    (net (code "163") (name "unconnected-(U1-PE15-Pad46)") (class "Default")
      (node (ref "U1") (pin "46") (pinfunction "PE15_46") (pintype "passive"))
    )
  )
)
